# decoder.net
KiCad netlist of a schematic drawn in EAGLE
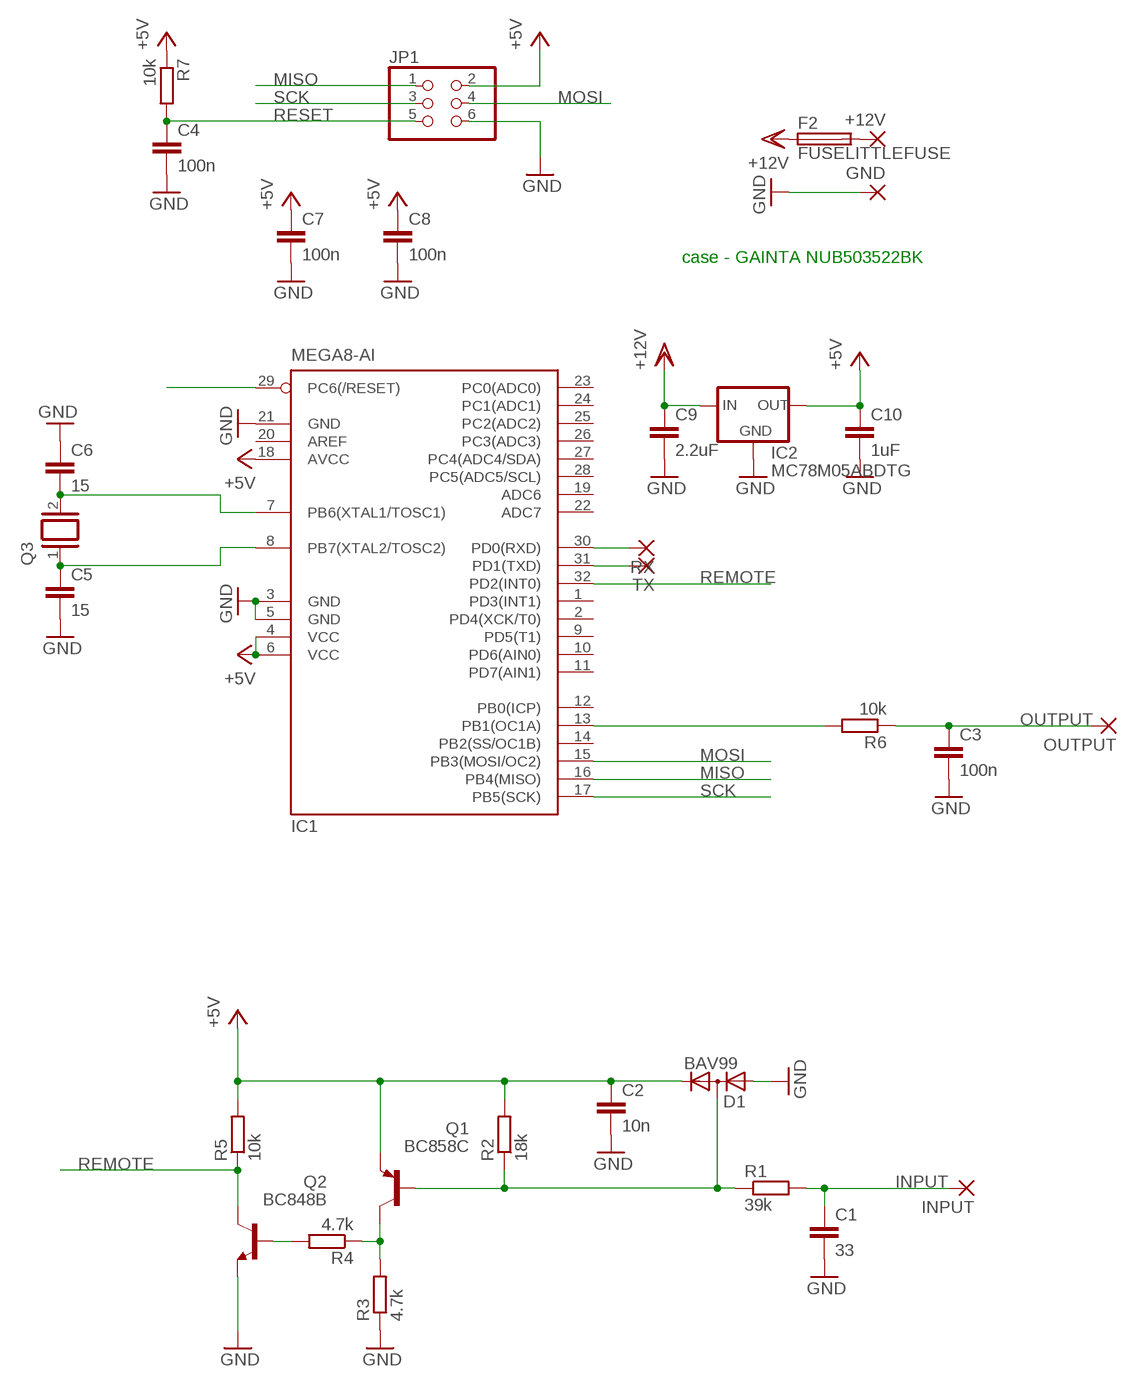
[diagram p0: schematic, sheet 1]

(export (version "E")
  (design (tool "Eeschema 10.0.6"))
  (components
    (comp (ref "+12V")
      (value "3,81/1,4")
      (footprint "eagle-import:3,81_1,4")
      (libsource (lib "eagle-import") (part "3,81/1,4"))
    )
    (comp (ref "C1")
      (value "33")
      (footprint "eagle-import:C0603")
      (libsource (lib "eagle-import") (part "C-EUC0603"))
    )
    (comp (ref "C2")
      (value "10n")
      (footprint "eagle-import:C0603")
      (libsource (lib "eagle-import") (part "C-EUC0603"))
    )
    (comp (ref "C3")
      (value "100n")
      (footprint "eagle-import:C0603")
      (libsource (lib "eagle-import") (part "C-EUC0603"))
    )
    (comp (ref "C4")
      (value "100n")
      (footprint "eagle-import:C0603")
      (libsource (lib "eagle-import") (part "C-EUC0603"))
    )
    (comp (ref "C5")
      (value "15")
      (footprint "eagle-import:C0603")
      (libsource (lib "eagle-import") (part "C-EUC0603"))
    )
    (comp (ref "C6")
      (value "15")
      (footprint "eagle-import:C0603")
      (libsource (lib "eagle-import") (part "C-EUC0603"))
    )
    (comp (ref "C7")
      (value "100n")
      (footprint "eagle-import:C0603")
      (libsource (lib "eagle-import") (part "C-EUC0603"))
    )
    (comp (ref "C8")
      (value "100n")
      (footprint "eagle-import:C0603")
      (libsource (lib "eagle-import") (part "C-EUC0603"))
    )
    (comp (ref "C9")
      (value "2.2uF")
      (footprint "eagle-import:C3225")
      (libsource (lib "eagle-import") (part "C-EUC3225"))
    )
    (comp (ref "C10")
      (value "1uF")
      (footprint "eagle-import:C1206")
      (libsource (lib "eagle-import") (part "C-EUC1206"))
    )
    (comp (ref "D1")
      (value "BAV99")
      (footprint "eagle-import:SOT23")
      (libsource (lib "eagle-import") (part "BAV199"))
    )
    (comp (ref "F2")
      (value "FUSELITTLEFUSE")
      (footprint "eagle-import:LITTLEFUSE")
      (libsource (lib "eagle-import") (part "FUSELITTLEFUSE"))
    )
    (comp (ref "GND")
      (value "3,81/1,4")
      (footprint "eagle-import:3,81_1,4")
      (libsource (lib "eagle-import") (part "3,81/1,4"))
    )
    (comp (ref "IC1")
      (value "MEGA8-AI")
      (footprint "eagle-import:TQFP32-08")
      (fields (field (name "MPN") "ATMEGA8-16AU"))
      (libsource (lib "eagle-import") (part "MEGA8-AI"))
    )
    (comp (ref "IC2")
      (value "MC78M05ABDTG")
      (footprint "eagle-import:DPACK")
      (libsource (lib "eagle-import") (part "LP2950?CDT-5.0"))
    )
    (comp (ref "INPUT")
      (value "2,54/1,1")
      (footprint "eagle-import:2,54_1,1")
      (libsource (lib "eagle-import") (part "2,54/1,1"))
    )
    (comp (ref "JP1")
      (value "PINHD-2X3")
      (footprint "eagle-import:2X03")
      (libsource (lib "eagle-import") (part "PINHD-2X3"))
    )
    (comp (ref "OUTPUT")
      (value "2,54/1,1")
      (footprint "eagle-import:2,54_1,1")
      (libsource (lib "eagle-import") (part "2,54/1,1"))
    )
    (comp (ref "Q1")
      (value "BC858C")
      (footprint "eagle-import:SOT23-BEC")
      (libsource (lib "eagle-import") (part "BC858SMDCLT1"))
    )
    (comp (ref "Q2")
      (value "BC848B")
      (footprint "eagle-import:SOT23")
      (libsource (lib "eagle-import") (part "BC848SMDB"))
    )
    (comp (ref "Q3")
      (value "XTAL/S")
      (footprint "eagle-import:QS")
      (libsource (lib "eagle-import") (part "XTAL/S"))
    )
    (comp (ref "R1")
      (value "39k")
      (footprint "eagle-import:R0603")
      (libsource (lib "eagle-import") (part "R-EU_R0603"))
    )
    (comp (ref "R2")
      (value "18k")
      (footprint "eagle-import:R0603")
      (libsource (lib "eagle-import") (part "R-EU_R0603"))
    )
    (comp (ref "R3")
      (value "4.7k")
      (footprint "eagle-import:R0603")
      (libsource (lib "eagle-import") (part "R-EU_R0603"))
    )
    (comp (ref "R4")
      (value "4.7k")
      (footprint "eagle-import:R0603")
      (libsource (lib "eagle-import") (part "R-EU_R0603"))
    )
    (comp (ref "R5")
      (value "10k")
      (footprint "eagle-import:R0603")
      (libsource (lib "eagle-import") (part "R-EU_R0603"))
    )
    (comp (ref "R6")
      (value "10k")
      (footprint "eagle-import:R0603")
      (libsource (lib "eagle-import") (part "R-EU_R0603"))
    )
    (comp (ref "R7")
      (value "10k")
      (footprint "eagle-import:R0603")
      (libsource (lib "eagle-import") (part "R-EU_R0603"))
    )
    (comp (ref "RX")
      (value "1,6/0,8")
      (footprint "eagle-import:1,6_0,8")
      (libsource (lib "eagle-import") (part "1,6/0,8"))
    )
    (comp (ref "TX")
      (value "1,6/0,8")
      (footprint "eagle-import:1,6_0,8")
      (libsource (lib "eagle-import") (part "1,6/0,8"))
    )
  )
  (nets
    (net (code "1") (name "+5V") (class "Default")
      (node (ref "C10") (pin "1") (pinfunction "1_1") (pintype "passive"))
      (node (ref "C2") (pin "1") (pinfunction "1_1") (pintype "passive"))
      (node (ref "C7") (pin "1") (pinfunction "1_1") (pintype "passive"))
      (node (ref "C8") (pin "1") (pinfunction "1_1") (pintype "passive"))
      (node (ref "D1") (pin "2") (pinfunction "C_2") (pintype "passive"))
      (node (ref "IC1") (pin "18") (pinfunction "AVCC_18") (pintype "power_in"))
      (node (ref "IC1") (pin "4") (pinfunction "VCC_4") (pintype "power_in"))
      (node (ref "IC1") (pin "6") (pinfunction "VCC_6") (pintype "power_in"))
      (node (ref "IC2") (pin "3") (pinfunction "OUT_3") (pintype "passive"))
      (node (ref "JP1") (pin "2") (pinfunction "2_2") (pintype "passive"))
      (node (ref "Q1") (pin "E") (pinfunction "E_E") (pintype "passive"))
      (node (ref "R2") (pin "2") (pinfunction "2_2") (pintype "passive"))
      (node (ref "R5") (pin "2") (pinfunction "2_2") (pintype "passive"))
      (node (ref "R7") (pin "1") (pinfunction "1_1") (pintype "passive"))
    )
    (net (code "2") (name "+12V") (class "Default")
      (node (ref "C9") (pin "1") (pinfunction "1_1") (pintype "passive"))
      (node (ref "F2") (pin "1") (pinfunction "1_1") (pintype "passive"))
      (node (ref "IC2") (pin "1") (pinfunction "IN_1") (pintype "input"))
    )
    (net (code "3") (name "/INPUT") (class "Default")
      (node (ref "C1") (pin "1") (pinfunction "1_1") (pintype "passive"))
      (node (ref "INPUT") (pin "1") (pinfunction "P_1") (pintype "passive"))
      (node (ref "R1") (pin "2") (pinfunction "2_2") (pintype "passive"))
    )
    (net (code "4") (name "/MISO") (class "Default")
      (node (ref "IC1") (pin "16") (pinfunction "PB4(MISO)_16") (pintype "bidirectional"))
      (node (ref "JP1") (pin "1") (pinfunction "1_1") (pintype "passive"))
    )
    (net (code "5") (name "/MOSI") (class "Default")
      (node (ref "IC1") (pin "15") (pinfunction "PB3(MOSI/OC2)_15") (pintype "bidirectional"))
      (node (ref "JP1") (pin "4") (pinfunction "4_4") (pintype "passive"))
    )
    (net (code "6") (name "/OUTPUT") (class "Default")
      (node (ref "C3") (pin "1") (pinfunction "1_1") (pintype "passive"))
      (node (ref "OUTPUT") (pin "1") (pinfunction "P_1") (pintype "passive"))
      (node (ref "R6") (pin "1") (pinfunction "1_1") (pintype "passive"))
    )
    (net (code "7") (name "/REMOTE") (class "Default")
      (node (ref "IC1") (pin "32") (pinfunction "PD2(INT0)_32") (pintype "bidirectional"))
      (node (ref "Q2") (pin "3") (pinfunction "C_3") (pintype "passive"))
      (node (ref "R5") (pin "1") (pinfunction "1_1") (pintype "passive"))
    )
    (net (code "8") (name "/RESET") (class "Default")
      (node (ref "C4") (pin "1") (pinfunction "1_1") (pintype "passive"))
      (node (ref "IC1") (pin "29") (pinfunction "PC6(/RESET)_29") (pintype "bidirectional"))
      (node (ref "JP1") (pin "5") (pinfunction "5_5") (pintype "passive"))
      (node (ref "R7") (pin "2") (pinfunction "2_2") (pintype "passive"))
    )
    (net (code "9") (name "/SCK") (class "Default")
      (node (ref "IC1") (pin "17") (pinfunction "PB5(SCK)_17") (pintype "bidirectional"))
      (node (ref "JP1") (pin "3") (pinfunction "3_3") (pintype "passive"))
    )
    (net (code "10") (name "GND") (class "Default")
      (node (ref "C1") (pin "2") (pinfunction "2_2") (pintype "passive"))
      (node (ref "C10") (pin "2") (pinfunction "2_2") (pintype "passive"))
      (node (ref "C2") (pin "2") (pinfunction "2_2") (pintype "passive"))
      (node (ref "C3") (pin "2") (pinfunction "2_2") (pintype "passive"))
      (node (ref "C4") (pin "2") (pinfunction "2_2") (pintype "passive"))
      (node (ref "C5") (pin "2") (pinfunction "2_2") (pintype "passive"))
      (node (ref "C6") (pin "1") (pinfunction "1_1") (pintype "passive"))
      (node (ref "C7") (pin "2") (pinfunction "2_2") (pintype "passive"))
      (node (ref "C8") (pin "2") (pinfunction "2_2") (pintype "passive"))
      (node (ref "C9") (pin "2") (pinfunction "2_2") (pintype "passive"))
      (node (ref "D1") (pin "1") (pinfunction "A_1") (pintype "passive"))
      (node (ref "GND") (pin "1") (pinfunction "P_1") (pintype "passive"))
      (node (ref "IC1") (pin "21") (pinfunction "GND_21") (pintype "power_in"))
      (node (ref "IC1") (pin "3") (pinfunction "GND_3") (pintype "power_in"))
      (node (ref "IC1") (pin "5") (pinfunction "GND_5") (pintype "power_in"))
      (node (ref "IC2") (pin "4") (pinfunction "GND_4") (pintype "input"))
      (node (ref "JP1") (pin "6") (pinfunction "6_6") (pintype "passive"))
      (node (ref "Q2") (pin "2") (pinfunction "E_2") (pintype "passive"))
      (node (ref "R3") (pin "1") (pinfunction "1_1") (pintype "passive"))
    )
    (net (code "11") (name "Net-(+12V-P)") (class "Default")
      (node (ref "+12V") (pin "1") (pinfunction "P_1") (pintype "passive"))
      (node (ref "F2") (pin "2") (pinfunction "2_2") (pintype "passive"))
    )
    (net (code "12") (name "Net-(D1-AC)") (class "Default")
      (node (ref "D1") (pin "3") (pinfunction "AC_3") (pintype "passive"))
      (node (ref "Q1") (pin "B") (pinfunction "B_B") (pintype "passive"))
      (node (ref "R1") (pin "1") (pinfunction "1_1") (pintype "passive"))
      (node (ref "R2") (pin "1") (pinfunction "1_1") (pintype "passive"))
    )
    (net (code "13") (name "Net-(IC1-PB1(OC1A))") (class "Default")
      (node (ref "IC1") (pin "13") (pinfunction "PB1(OC1A)_13") (pintype "bidirectional"))
      (node (ref "R6") (pin "2") (pinfunction "2_2") (pintype "passive"))
    )
    (net (code "14") (name "Net-(IC1-PB6(XTAL1{slash}TOSC1))") (class "Default")
      (node (ref "C6") (pin "2") (pinfunction "2_2") (pintype "passive"))
      (node (ref "IC1") (pin "7") (pinfunction "PB6(XTAL1/TOSC1)_7") (pintype "bidirectional"))
      (node (ref "Q3") (pin "2") (pinfunction "2_2") (pintype "passive"))
    )
    (net (code "15") (name "Net-(IC1-PB7(XTAL2{slash}TOSC2))") (class "Default")
      (node (ref "C5") (pin "1") (pinfunction "1_1") (pintype "passive"))
      (node (ref "IC1") (pin "8") (pinfunction "PB7(XTAL2/TOSC2)_8") (pintype "bidirectional"))
      (node (ref "Q3") (pin "1") (pinfunction "1_1") (pintype "passive"))
    )
    (net (code "16") (name "Net-(IC1-PD0(RXD))") (class "Default")
      (node (ref "IC1") (pin "30") (pinfunction "PD0(RXD)_30") (pintype "bidirectional"))
      (node (ref "RX") (pin "1") (pinfunction "P_1") (pintype "passive"))
    )
    (net (code "17") (name "Net-(IC1-PD1(TXD))") (class "Default")
      (node (ref "IC1") (pin "31") (pinfunction "PD1(TXD)_31") (pintype "bidirectional"))
      (node (ref "TX") (pin "1") (pinfunction "P_1") (pintype "passive"))
    )
    (net (code "18") (name "Net-(Q1-PadC)") (class "Default")
      (node (ref "Q1") (pin "C") (pinfunction "C_C") (pintype "passive"))
      (node (ref "R3") (pin "2") (pinfunction "2_2") (pintype "passive"))
      (node (ref "R4") (pin "1") (pinfunction "1_1") (pintype "passive"))
    )
    (net (code "19") (name "Net-(Q2-B)") (class "Default")
      (node (ref "Q2") (pin "1") (pinfunction "B_1") (pintype "passive"))
      (node (ref "R4") (pin "2") (pinfunction "2_2") (pintype "passive"))
    )
    (net (code "20") (name "unconnected-(IC1-ADC6-Pad19)") (class "Default")
      (node (ref "IC1") (pin "19") (pinfunction "ADC6_19") (pintype "bidirectional"))
    )
    (net (code "21") (name "unconnected-(IC1-ADC7-Pad22)") (class "Default")
      (node (ref "IC1") (pin "22") (pinfunction "ADC7_22") (pintype "bidirectional"))
    )
    (net (code "22") (name "unconnected-(IC1-AREF-Pad20)") (class "Default")
      (node (ref "IC1") (pin "20") (pinfunction "AREF_20") (pintype "passive"))
    )
    (net (code "23") (name "unconnected-(IC1-PB0(ICP)-Pad12)") (class "Default")
      (node (ref "IC1") (pin "12") (pinfunction "PB0(ICP)_12") (pintype "bidirectional"))
    )
    (net (code "24") (name "unconnected-(IC1-PB2(SS{slash}OC1B)-Pad14)") (class "Default")
      (node (ref "IC1") (pin "14") (pinfunction "PB2(SS/OC1B)_14") (pintype "bidirectional"))
    )
    (net (code "25") (name "unconnected-(IC1-PC0(ADC0)-Pad23)") (class "Default")
      (node (ref "IC1") (pin "23") (pinfunction "PC0(ADC0)_23") (pintype "bidirectional"))
    )
    (net (code "26") (name "unconnected-(IC1-PC1(ADC1)-Pad24)") (class "Default")
      (node (ref "IC1") (pin "24") (pinfunction "PC1(ADC1)_24") (pintype "bidirectional"))
    )
    (net (code "27") (name "unconnected-(IC1-PC2(ADC2)-Pad25)") (class "Default")
      (node (ref "IC1") (pin "25") (pinfunction "PC2(ADC2)_25") (pintype "bidirectional"))
    )
    (net (code "28") (name "unconnected-(IC1-PC3(ADC3)-Pad26)") (class "Default")
      (node (ref "IC1") (pin "26") (pinfunction "PC3(ADC3)_26") (pintype "bidirectional"))
    )
    (net (code "29") (name "unconnected-(IC1-PC4(ADC4{slash}SDA)-Pad27)") (class "Default")
      (node (ref "IC1") (pin "27") (pinfunction "PC4(ADC4/SDA)_27") (pintype "bidirectional"))
    )
    (net (code "30") (name "unconnected-(IC1-PC5(ADC5{slash}SCL)-Pad28)") (class "Default")
      (node (ref "IC1") (pin "28") (pinfunction "PC5(ADC5/SCL)_28") (pintype "bidirectional"))
    )
    (net (code "31") (name "unconnected-(IC1-PD3(INT1)-Pad1)") (class "Default")
      (node (ref "IC1") (pin "1") (pinfunction "PD3(INT1)_1") (pintype "bidirectional"))
    )
    (net (code "32") (name "unconnected-(IC1-PD4(XCK{slash}T0)-Pad2)") (class "Default")
      (node (ref "IC1") (pin "2") (pinfunction "PD4(XCK/T0)_2") (pintype "bidirectional"))
    )
    (net (code "33") (name "unconnected-(IC1-PD5(T1)-Pad9)") (class "Default")
      (node (ref "IC1") (pin "9") (pinfunction "PD5(T1)_9") (pintype "bidirectional"))
    )
    (net (code "34") (name "unconnected-(IC1-PD6(AIN0)-Pad10)") (class "Default")
      (node (ref "IC1") (pin "10") (pinfunction "PD6(AIN0)_10") (pintype "bidirectional"))
    )
    (net (code "35") (name "unconnected-(IC1-PD7(AIN1)-Pad11)") (class "Default")
      (node (ref "IC1") (pin "11") (pinfunction "PD7(AIN1)_11") (pintype "bidirectional"))
    )
  )
)
